# 01_-_Main.net
KiCad netlist of a schematic drawn in Altium Designer
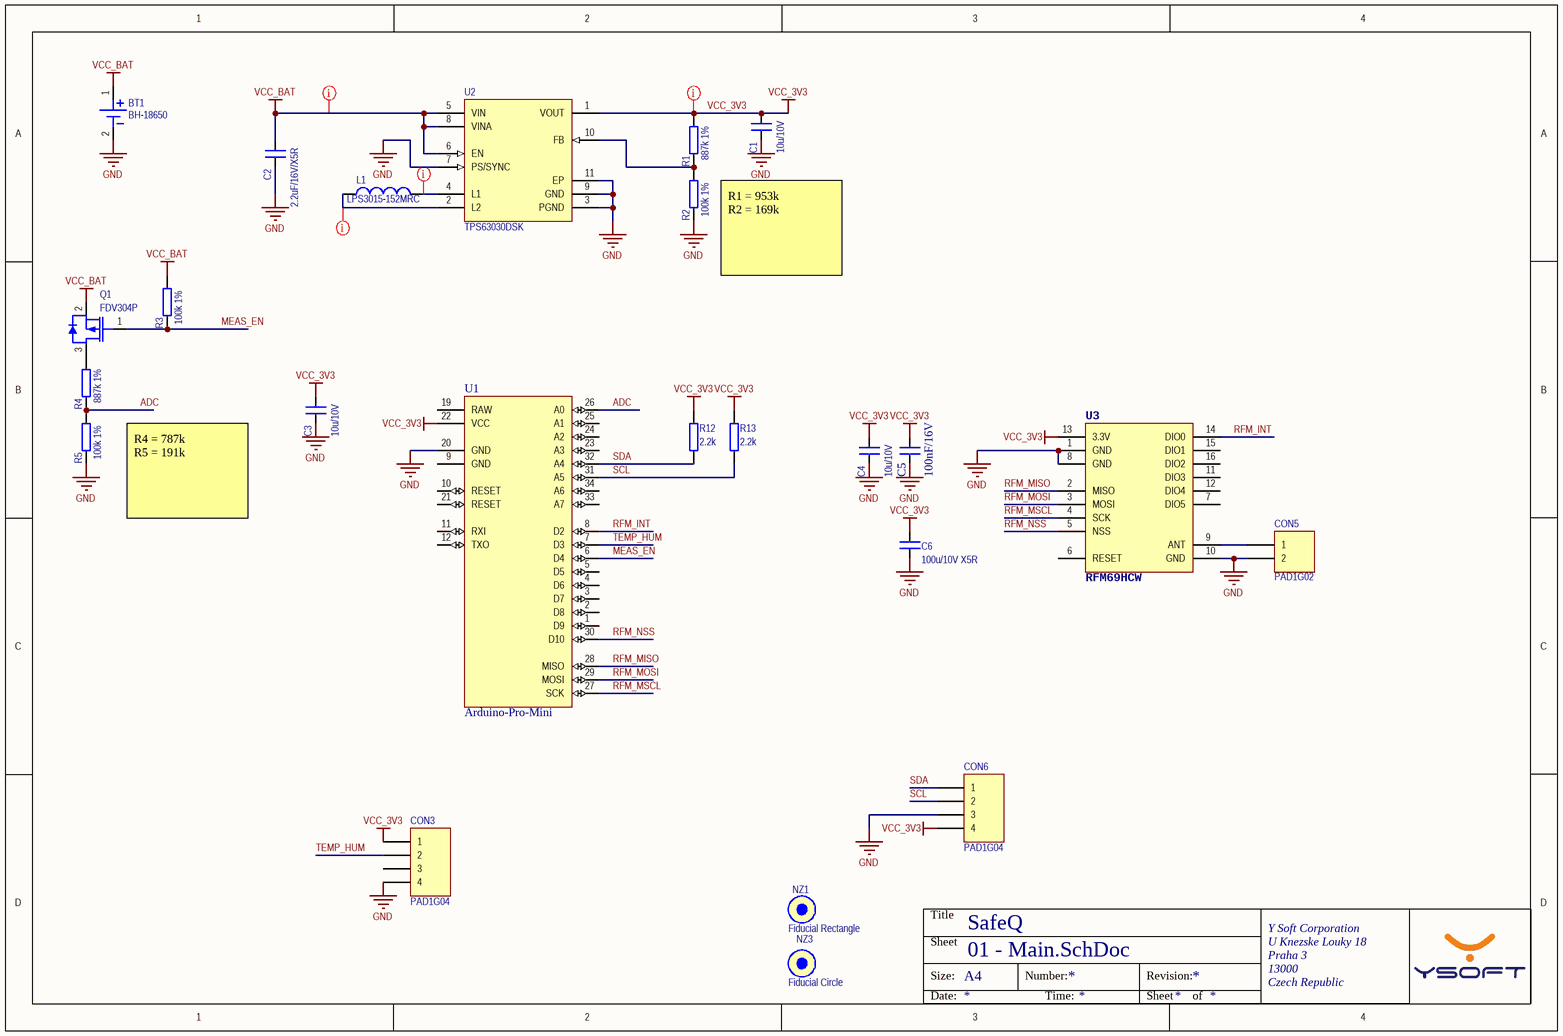
[diagram p0: 01 - Main.SchDoc]

(export (version "E")
  (design (tool "Eeschema 10.0.6"))
  (components
    (comp (ref "BT1") (value "BH-18650") (footprint "BH18650") (libsource (lib "Battery") (part "BH-18650")))
    (comp (ref "C1")
      (value "10u/10V")
      (footprint "C-0805")
      (description "SMD Ceramic Capacitor 0805 10u/10V")
      (libsource (lib "Personal Vault") (part "CapacitorNP"))
    )
    (comp (ref "C2")
      (value "2.2uF/16V/X5R")
      (footprint "C-0603")
      (description "SMD Ceramic Capacitor 0603 2.2uF/16V/X5R")
      (libsource (lib "Personal Vault") (part "CapacitorNP"))
    )
    (comp (ref "C3")
      (value "10u/10V")
      (footprint "C-0805")
      (description "SMD Ceramic Capacitor 0805 10u/10V")
      (libsource (lib "Personal Vault") (part "CapacitorNP"))
    )
    (comp (ref "C4")
      (value "10u/10V")
      (footprint "C-0805")
      (description "SMD Ceramic Capacitor 0805 10u/10V")
      (libsource (lib "Personal Vault") (part "CapacitorNP"))
    )
    (comp (ref "C5")
      (value "100nF/16V")
      (footprint "C-0603")
      (description "SMD Ceramic Capacitor 0603 100nF/16V")
      (libsource (lib "Personal Vault") (part "CapacitorNP"))
    )
    (comp (ref "C6")
      (value "100u/10V X5R")
      (footprint "C-1206")
      (description "SMD Ceramic Capacitor 1206 100u/10V X5R")
      (libsource (lib "Personal Vault") (part "CapacitorNP"))
    )
    (comp (ref "CON3")
      (value "PAD1G04")
      (footprint "HDR1X04S")
      (description "1x4pin single row pads, 2.54mm")
      (libsource (lib "Personal Vault") (part "Header 4"))
    )
    (comp (ref "CON5")
      (value "PAD1G02")
      (footprint "HDR1X02S")
      (description "1x2pin single row pads, 2.54mm")
      (fields (field (name "PUBLISHER") "Altium Limited"))
      (libsource (lib "Personal Vault") (part "Header 2"))
    )
    (comp (ref "CON6")
      (value "PAD1G04")
      (footprint "HDR1X04S")
      (description "1x4pin single row pads, 2.54mm")
      (libsource (lib "Personal Vault") (part "Header 4"))
    )
    (comp (ref "L1")
      (value "LPS3015-152MRC")
      (footprint "LPS3015")
      (description "Shielded inductor 1.5uH/1.3A 3x3mm")
      (libsource (lib "Personal Vault") (part "Inductor"))
    )
    (comp (ref "NZ1")
      (value "Fiducial Rectangle")
      (footprint "Fiducial Rectangle")
      (libsource (lib "Personal Vault") (part "Fiducial Mark"))
    )
    (comp (ref "NZ3")
      (value "Fiducial Circle")
      (footprint "Fiducial Circle")
      (libsource (lib "Personal Vault") (part "Fiducial Mark"))
    )
    (comp (ref "Q1")
      (value "FDV304P")
      (footprint "SOT23-3L")
      (description "P-Channel Digital FET 25V, 460mA")
      (libsource (lib "Personal Vault") (part "P-MOSFET"))
    )
    (comp (ref "R1")
      (value "887k 1%")
      (footprint "R-0603")
      (description "SMD Resistor 0603 887k 1%")
      (libsource (lib "Personal Vault") (part "Resistor"))
    )
    (comp (ref "R2")
      (value "100k 1%")
      (footprint "R-0603")
      (description "SMD Resistor 0603 100k 1%")
      (libsource (lib "Personal Vault") (part "Resistor"))
    )
    (comp (ref "R3")
      (value "100k 1%")
      (footprint "R-0603")
      (description "SMD Resistor 0603 100k 1%")
      (libsource (lib "Personal Vault") (part "Resistor"))
    )
    (comp (ref "R4")
      (value "887k 1%")
      (footprint "R-0603")
      (description "SMD Resistor 0603 887k 1%")
      (libsource (lib "Personal Vault") (part "Resistor"))
    )
    (comp (ref "R5")
      (value "100k 1%")
      (footprint "R-0603")
      (description "SMD Resistor 0603 100k 1%")
      (libsource (lib "Personal Vault") (part "Resistor"))
    )
    (comp (ref "R12")
      (value "2.2k")
      (footprint "R-0603")
      (description "SMD Resistor 0603 2k2")
      (libsource (lib "Personal Vault") (part "Resistor"))
    )
    (comp (ref "R13")
      (value "2.2k")
      (footprint "R-0603")
      (description "SMD Resistor 0603 2k2")
      (libsource (lib "Personal Vault") (part "Resistor"))
    )
    (comp (ref "U1")
      (value "Arduino-Pro-Mini")
      (footprint "Arduino Mini Pro")
      (libsource (lib "Arduino") (part "Arduino-Pro-Mini"))
    )
    (comp (ref "U2")
      (value "TPS63030DSK")
      (footprint "DSK10-2000X1200TP_V")
      (description "High Efficient Single Inductor Buck-Boost Converter with 1-A Switches")
      (libsource (lib "Personal Vault") (part "TPS63030"))
    )
    (comp (ref "U3")
      (value "RFM69HCW")
      (footprint "RFM:RFM69HCW-XXXS2")
      (libsource (lib "RFM") (part "RFM69HCW"))
    )
  )
  (nets
    (net (code "1") (name "/ADC") (class "Default")
      (node (ref "R4") (pin "1") (pinfunction "1_1") (pintype "passive"))
      (node (ref "R5") (pin "2") (pinfunction "2_2") (pintype "passive"))
      (node (ref "U1") (pin "26") (pinfunction "A0_26") (pintype "bidirectional"))
    )
    (net (code "2") (name "/MEAS_EN") (class "Default")
      (node (ref "Q1") (pin "1") (pinfunction "GATE_1") (pintype "passive"))
      (node (ref "R3") (pin "1") (pinfunction "1_1") (pintype "passive"))
      (node (ref "U1") (pin "6") (pinfunction "D4_6") (pintype "bidirectional"))
    )
    (net (code "3") (name "/RFM_INT") (class "Default")
      (node (ref "U1") (pin "8") (pinfunction "D2_8") (pintype "bidirectional"))
      (node (ref "U3") (pin "14") (pinfunction "DIO0_14") (pintype "passive"))
    )
    (net (code "4") (name "/RFM_MISO") (class "Default")
      (node (ref "U1") (pin "28") (pinfunction "MISO_28") (pintype "bidirectional"))
      (node (ref "U3") (pin "2") (pinfunction "MISO_2") (pintype "passive"))
    )
    (net (code "5") (name "/RFM_MOSI") (class "Default")
      (node (ref "U1") (pin "29") (pinfunction "MOSI_29") (pintype "bidirectional"))
      (node (ref "U3") (pin "3") (pinfunction "MOSI_3") (pintype "passive"))
    )
    (net (code "6") (name "/RFM_MSCL") (class "Default")
      (node (ref "U1") (pin "27") (pinfunction "SCK_27") (pintype "bidirectional"))
      (node (ref "U3") (pin "4") (pinfunction "SCK_4") (pintype "passive"))
    )
    (net (code "7") (name "/RFM_NSS") (class "Default")
      (node (ref "U1") (pin "30") (pinfunction "D10_30") (pintype "bidirectional"))
      (node (ref "U3") (pin "5") (pinfunction "NSS_5") (pintype "passive"))
    )
    (net (code "8") (name "/SCL") (class "Default")
      (node (ref "CON6") (pin "2") (pinfunction "2_2") (pintype "passive"))
      (node (ref "R13") (pin "1") (pinfunction "1_1") (pintype "passive"))
      (node (ref "U1") (pin "31") (pinfunction "A5_31") (pintype "bidirectional"))
    )
    (net (code "9") (name "/SDA") (class "Default")
      (node (ref "CON6") (pin "1") (pinfunction "1_1") (pintype "passive"))
      (node (ref "R12") (pin "1") (pinfunction "1_1") (pintype "passive"))
      (node (ref "U1") (pin "32") (pinfunction "A4_32") (pintype "bidirectional"))
    )
    (net (code "10") (name "/TEMP_HUM") (class "Default")
      (node (ref "CON3") (pin "2") (pinfunction "2_2") (pintype "passive"))
      (node (ref "U1") (pin "7") (pinfunction "D3_7") (pintype "bidirectional"))
    )
    (net (code "11") (name "GND") (class "Default")
      (node (ref "BT1") (pin "2") (pinfunction "-_2") (pintype "passive"))
      (node (ref "C1") (pin "1") (pinfunction "1_1") (pintype "passive"))
      (node (ref "C2") (pin "1") (pinfunction "1_1") (pintype "passive"))
      (node (ref "C3") (pin "1") (pinfunction "1_1") (pintype "passive"))
      (node (ref "C4") (pin "1") (pinfunction "1_1") (pintype "passive"))
      (node (ref "C5") (pin "1") (pinfunction "1_1") (pintype "passive"))
      (node (ref "C6") (pin "1") (pinfunction "1_1") (pintype "passive"))
      (node (ref "CON3") (pin "4") (pinfunction "4_4") (pintype "passive"))
      (node (ref "CON5") (pin "2") (pinfunction "2_2") (pintype "passive"))
      (node (ref "CON6") (pin "3") (pinfunction "3_3") (pintype "passive"))
      (node (ref "R2") (pin "1") (pinfunction "1_1") (pintype "passive"))
      (node (ref "R5") (pin "1") (pinfunction "1_1") (pintype "passive"))
      (node (ref "U1") (pin "20") (pinfunction "GND_20") (pintype "power_in"))
      (node (ref "U2") (pin "11") (pinfunction "EP_11") (pintype "power_in"))
      (node (ref "U2") (pin "3") (pinfunction "PGND_3") (pintype "power_in"))
      (node (ref "U2") (pin "7") (pinfunction "PS/SYNC_7") (pintype "input"))
      (node (ref "U2") (pin "9") (pinfunction "GND_9") (pintype "power_in"))
      (node (ref "U3") (pin "1") (pinfunction "GND_1") (pintype "power_in"))
      (node (ref "U3") (pin "10") (pinfunction "GND_10") (pintype "power_in"))
      (node (ref "U3") (pin "8") (pinfunction "GND_8") (pintype "power_in"))
    )
    (net (code "12") (name "Net-(Q1-DRAIN)") (class "Default")
      (node (ref "Q1") (pin "3") (pinfunction "DRAIN_3") (pintype "passive"))
      (node (ref "R4") (pin "2") (pinfunction "2_2") (pintype "passive"))
    )
    (net (code "13") (name "Net-(U2-FB)") (class "Default")
      (node (ref "R1") (pin "1") (pinfunction "1_1") (pintype "passive"))
      (node (ref "R2") (pin "2") (pinfunction "2_2") (pintype "passive"))
      (node (ref "U2") (pin "10") (pinfunction "FB_10") (pintype "input"))
    )
    (net (code "14") (name "Net-(U2-L1)") (class "Default")
      (node (ref "L1") (pin "2") (pinfunction "2_2") (pintype "passive"))
      (node (ref "U2") (pin "4") (pinfunction "L1_4") (pintype "passive"))
    )
    (net (code "15") (name "Net-(U2-L2)") (class "Default")
      (node (ref "L1") (pin "1") (pinfunction "1_1") (pintype "passive"))
      (node (ref "U2") (pin "2") (pinfunction "L2_2") (pintype "passive"))
    )
    (net (code "16") (name "Net-(U3-ANT)") (class "Default")
      (node (ref "CON5") (pin "1") (pinfunction "1_1") (pintype "passive"))
      (node (ref "U3") (pin "9") (pinfunction "ANT_9") (pintype "passive"))
    )
    (net (code "17") (name "VCC_3V3") (class "Default")
      (node (ref "C1") (pin "2") (pinfunction "2_2") (pintype "passive"))
      (node (ref "C3") (pin "2") (pinfunction "2_2") (pintype "passive"))
      (node (ref "C4") (pin "2") (pinfunction "2_2") (pintype "passive"))
      (node (ref "C5") (pin "2") (pinfunction "2_2") (pintype "passive"))
      (node (ref "C6") (pin "2") (pinfunction "2_2") (pintype "passive"))
      (node (ref "CON3") (pin "1") (pinfunction "1_1") (pintype "passive"))
      (node (ref "CON6") (pin "4") (pinfunction "4_4") (pintype "passive"))
      (node (ref "R1") (pin "2") (pinfunction "2_2") (pintype "passive"))
      (node (ref "R12") (pin "2") (pinfunction "2_2") (pintype "passive"))
      (node (ref "R13") (pin "2") (pinfunction "2_2") (pintype "passive"))
      (node (ref "U1") (pin "22") (pinfunction "VCC_22") (pintype "power_in"))
      (node (ref "U2") (pin "1") (pinfunction "VOUT_1") (pintype "power_in"))
      (node (ref "U3") (pin "13") (pinfunction "3.3V_13") (pintype "power_in"))
    )
    (net (code "18") (name "VCC_BAT") (class "Default")
      (node (ref "BT1") (pin "1") (pinfunction "+_1") (pintype "passive"))
      (node (ref "C2") (pin "2") (pinfunction "2_2") (pintype "passive"))
      (node (ref "Q1") (pin "2") (pinfunction "SOURCE_2") (pintype "passive"))
      (node (ref "R3") (pin "2") (pinfunction "2_2") (pintype "passive"))
      (node (ref "U2") (pin "5") (pinfunction "VIN_5") (pintype "power_in"))
      (node (ref "U2") (pin "6") (pinfunction "EN_6") (pintype "input"))
      (node (ref "U2") (pin "8") (pinfunction "VINA_8") (pintype "power_in"))
    )
    (net (code "19") (name "unconnected-(CON3-Pad3)") (class "Default")
      (node (ref "CON3") (pin "3") (pinfunction "3_3") (pintype "passive"))
    )
    (net (code "20") (name "unconnected-(U1-A1-Pad25)") (class "Default")
      (node (ref "U1") (pin "25") (pinfunction "A1_25") (pintype "bidirectional"))
    )
    (net (code "21") (name "unconnected-(U1-A2-Pad24)") (class "Default")
      (node (ref "U1") (pin "24") (pinfunction "A2_24") (pintype "bidirectional"))
    )
    (net (code "22") (name "unconnected-(U1-A3-Pad23)") (class "Default")
      (node (ref "U1") (pin "23") (pinfunction "A3_23") (pintype "bidirectional"))
    )
    (net (code "23") (name "unconnected-(U1-A6-Pad34)") (class "Default")
      (node (ref "U1") (pin "34") (pinfunction "A6_34") (pintype "bidirectional"))
    )
    (net (code "24") (name "unconnected-(U1-A7-Pad33)") (class "Default")
      (node (ref "U1") (pin "33") (pinfunction "A7_33") (pintype "bidirectional"))
    )
    (net (code "25") (name "unconnected-(U1-D5-Pad5)") (class "Default")
      (node (ref "U1") (pin "5") (pinfunction "D5_5") (pintype "bidirectional"))
    )
    (net (code "26") (name "unconnected-(U1-D6-Pad4)") (class "Default")
      (node (ref "U1") (pin "4") (pinfunction "D6_4") (pintype "bidirectional"))
    )
    (net (code "27") (name "unconnected-(U1-D7-Pad3)") (class "Default")
      (node (ref "U1") (pin "3") (pinfunction "D7_3") (pintype "bidirectional"))
    )
    (net (code "28") (name "unconnected-(U1-D8-Pad2)") (class "Default")
      (node (ref "U1") (pin "2") (pinfunction "D8_2") (pintype "bidirectional"))
    )
    (net (code "29") (name "unconnected-(U1-D9-Pad1)") (class "Default")
      (node (ref "U1") (pin "1") (pinfunction "D9_1") (pintype "bidirectional"))
    )
    (net (code "30") (name "unconnected-(U1-GND-Pad9)") (class "Default")
      (node (ref "U1") (pin "9") (pinfunction "GND_9") (pintype "power_in"))
    )
    (net (code "31") (name "unconnected-(U1-RAW-Pad19)") (class "Default")
      (node (ref "U1") (pin "19") (pinfunction "RAW_19") (pintype "power_in"))
    )
    (net (code "32") (name "unconnected-(U1-RESET-Pad10)") (class "Default")
      (node (ref "U1") (pin "10") (pinfunction "RESET_10") (pintype "bidirectional"))
    )
    (net (code "33") (name "unconnected-(U1-RESET-Pad21)") (class "Default")
      (node (ref "U1") (pin "21") (pinfunction "RESET_21") (pintype "bidirectional"))
    )
    (net (code "34") (name "unconnected-(U1-RXI-Pad11)") (class "Default")
      (node (ref "U1") (pin "11") (pinfunction "RXI_11") (pintype "bidirectional"))
    )
    (net (code "35") (name "unconnected-(U1-TXO-Pad12)") (class "Default")
      (node (ref "U1") (pin "12") (pinfunction "TXO_12") (pintype "bidirectional"))
    )
    (net (code "36") (name "unconnected-(U3-DIO1-Pad15)") (class "Default")
      (node (ref "U3") (pin "15") (pinfunction "DIO1_15") (pintype "passive"))
    )
    (net (code "37") (name "unconnected-(U3-DIO2-Pad16)") (class "Default")
      (node (ref "U3") (pin "16") (pinfunction "DIO2_16") (pintype "passive"))
    )
    (net (code "38") (name "unconnected-(U3-DIO3-Pad11)") (class "Default")
      (node (ref "U3") (pin "11") (pinfunction "DIO3_11") (pintype "passive"))
    )
    (net (code "39") (name "unconnected-(U3-DIO4-Pad12)") (class "Default")
      (node (ref "U3") (pin "12") (pinfunction "DIO4_12") (pintype "passive"))
    )
    (net (code "40") (name "unconnected-(U3-DIO5-Pad7)") (class "Default")
      (node (ref "U3") (pin "7") (pinfunction "DIO5_7") (pintype "passive"))
    )
    (net (code "41") (name "unconnected-(U3-RESET-Pad6)") (class "Default")
      (node (ref "U3") (pin "6") (pinfunction "RESET_6") (pintype "passive"))
    )
  )
)
